# clock.net
KiCad netlist of a schematic drawn in EAGLE
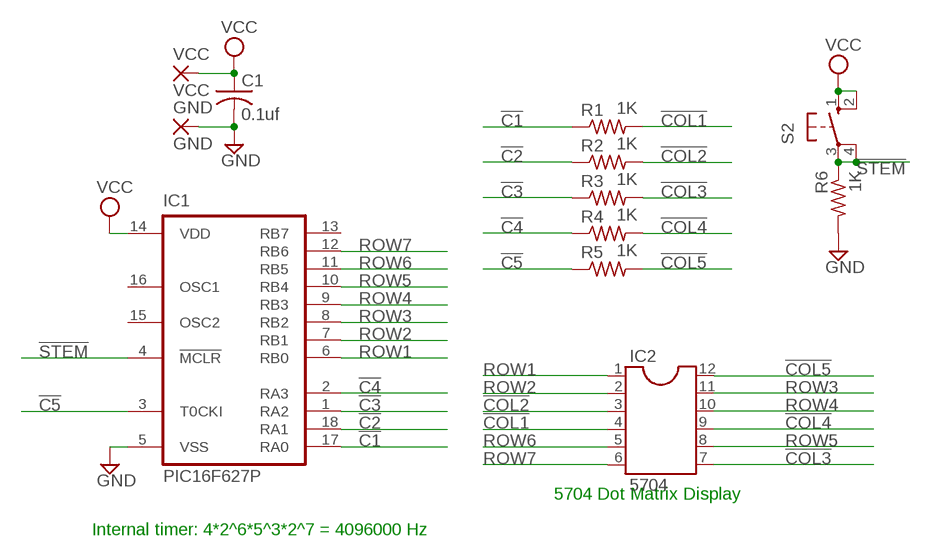
[diagram p0: schematic, sheet 1]

(export (version "E")
  (design (tool "Eeschema 10.0.6"))
  (components
    (comp (ref "C1")
      (value "0.1uf")
      (footprint "eagle-import:C025-025X050")
      (libsource (lib "eagle-import") (part "C-US025-025X050"))
    )
    (comp (ref "GND")
      (value "GND")
      (footprint "eagle-import:1,6_0,8")
      (libsource (lib "eagle-import") (part "1,6/0,8"))
    )
    (comp (ref "IC1")
      (value "PIC16F627P")
      (footprint "eagle-import:DIL18")
      (fields (field (name "MF") "MICROCHIP") (field (name "MPN") "PIC16C622A-04I/P"))
      (libsource (lib "eagle-import") (part "PIC16CP622"))
    )
    (comp (ref "IC2")
      (value "5704")
      (footprint "eagle-import:DIL12")
      (libsource (lib "eagle-import") (part "DIL12"))
    )
    (comp (ref "R1")
      (value "1K")
      (footprint "eagle-import:0207_10")
      (libsource (lib "eagle-import") (part "R-US_0207/10"))
    )
    (comp (ref "R2")
      (value "1K")
      (footprint "eagle-import:0207_10")
      (libsource (lib "eagle-import") (part "R-US_0207/10"))
    )
    (comp (ref "R3")
      (value "1K")
      (footprint "eagle-import:0207_10")
      (libsource (lib "eagle-import") (part "R-US_0207/10"))
    )
    (comp (ref "R4")
      (value "1K")
      (footprint "eagle-import:0207_10")
      (libsource (lib "eagle-import") (part "R-US_0207/10"))
    )
    (comp (ref "R5")
      (value "1K")
      (footprint "eagle-import:0207_10")
      (libsource (lib "eagle-import") (part "R-US_0207/10"))
    )
    (comp (ref "R6")
      (value "1K")
      (footprint "eagle-import:0207_10")
      (libsource (lib "eagle-import") (part "R-US_0207/10"))
    )
    (comp (ref "S2")
      (value "10-XX")
      (footprint "eagle-import:B3F-10XX")
      (fields (field (name "MPN") "B3F-1000"))
      (libsource (lib "eagle-import") (part "10-XX"))
    )
    (comp (ref "VCC")
      (value "VCC")
      (footprint "eagle-import:1,6_0,8")
      (libsource (lib "eagle-import") (part "1,6/0,8"))
    )
  )
  (nets
    (net (code "1") (name "/ROW1") (class "Default")
      (node (ref "IC1") (pin "6") (pinfunction "RB0_6") (pintype "bidirectional"))
      (node (ref "IC2") (pin "1") (pinfunction "1_1") (pintype "passive"))
    )
    (net (code "2") (name "/ROW2") (class "Default")
      (node (ref "IC1") (pin "7") (pinfunction "RB1_7") (pintype "bidirectional"))
      (node (ref "IC2") (pin "2") (pinfunction "2_2") (pintype "passive"))
    )
    (net (code "3") (name "/ROW3") (class "Default")
      (node (ref "IC1") (pin "8") (pinfunction "RB2_8") (pintype "bidirectional"))
      (node (ref "IC2") (pin "11") (pinfunction "11_11") (pintype "passive"))
    )
    (net (code "4") (name "/ROW4") (class "Default")
      (node (ref "IC1") (pin "9") (pinfunction "RB3_9") (pintype "bidirectional"))
      (node (ref "IC2") (pin "10") (pinfunction "10_10") (pintype "passive"))
    )
    (net (code "5") (name "/ROW5") (class "Default")
      (node (ref "IC1") (pin "10") (pinfunction "RB4_10") (pintype "bidirectional"))
      (node (ref "IC2") (pin "8") (pinfunction "8_8") (pintype "passive"))
    )
    (net (code "6") (name "/ROW6") (class "Default")
      (node (ref "IC1") (pin "11") (pinfunction "RB5_11") (pintype "bidirectional"))
      (node (ref "IC2") (pin "5") (pinfunction "5_5") (pintype "passive"))
    )
    (net (code "7") (name "/ROW7") (class "Default")
      (node (ref "IC1") (pin "12") (pinfunction "RB6_12") (pintype "bidirectional"))
      (node (ref "IC2") (pin "6") (pinfunction "6_6") (pintype "passive"))
    )
    (net (code "8") (name "/~{C1}") (class "Default")
      (node (ref "IC1") (pin "17") (pinfunction "RA0_17") (pintype "bidirectional"))
      (node (ref "R1") (pin "1") (pinfunction "1_1") (pintype "passive"))
    )
    (net (code "9") (name "/~{C2}") (class "Default")
      (node (ref "IC1") (pin "18") (pinfunction "RA1_18") (pintype "bidirectional"))
      (node (ref "R2") (pin "1") (pinfunction "1_1") (pintype "passive"))
    )
    (net (code "10") (name "/~{C3}") (class "Default")
      (node (ref "IC1") (pin "1") (pinfunction "RA2_1") (pintype "bidirectional"))
      (node (ref "R3") (pin "1") (pinfunction "1_1") (pintype "passive"))
    )
    (net (code "11") (name "/~{C4}") (class "Default")
      (node (ref "IC1") (pin "2") (pinfunction "RA3_2") (pintype "bidirectional"))
      (node (ref "R4") (pin "1") (pinfunction "1_1") (pintype "passive"))
    )
    (net (code "12") (name "/~{C5}") (class "Default")
      (node (ref "IC1") (pin "3") (pinfunction "T0CKI_3") (pintype "input"))
      (node (ref "R5") (pin "1") (pinfunction "1_1") (pintype "passive"))
    )
    (net (code "13") (name "/~{COL1}") (class "Default")
      (node (ref "IC2") (pin "4") (pinfunction "4_4") (pintype "passive"))
      (node (ref "R1") (pin "2") (pinfunction "2_2") (pintype "passive"))
    )
    (net (code "14") (name "/~{COL2}") (class "Default")
      (node (ref "IC2") (pin "3") (pinfunction "3_3") (pintype "passive"))
      (node (ref "R2") (pin "2") (pinfunction "2_2") (pintype "passive"))
    )
    (net (code "15") (name "/~{COL3}") (class "Default")
      (node (ref "IC2") (pin "7") (pinfunction "7_7") (pintype "passive"))
      (node (ref "R3") (pin "2") (pinfunction "2_2") (pintype "passive"))
    )
    (net (code "16") (name "/~{COL4}") (class "Default")
      (node (ref "IC2") (pin "9") (pinfunction "9_9") (pintype "passive"))
      (node (ref "R4") (pin "2") (pinfunction "2_2") (pintype "passive"))
    )
    (net (code "17") (name "/~{COL5}") (class "Default")
      (node (ref "IC2") (pin "12") (pinfunction "12_12") (pintype "passive"))
      (node (ref "R5") (pin "2") (pinfunction "2_2") (pintype "passive"))
    )
    (net (code "18") (name "/~{STEM}") (class "Default")
      (node (ref "IC1") (pin "4") (pinfunction "~{MCLR}_4") (pintype "input"))
      (node (ref "R6") (pin "1") (pinfunction "1_1") (pintype "passive"))
      (node (ref "S2") (pin "3") (pinfunction "P_3") (pintype "passive"))
      (node (ref "S2") (pin "4") (pinfunction "P1_4") (pintype "passive"))
    )
    (net (code "19") (name "GND") (class "Default")
      (node (ref "C1") (pin "2") (pinfunction "2_2") (pintype "passive"))
      (node (ref "GND") (pin "1") (pinfunction "P_1") (pintype "passive"))
      (node (ref "IC1") (pin "5") (pinfunction "VSS_5") (pintype "power_in"))
      (node (ref "R6") (pin "2") (pinfunction "2_2") (pintype "passive"))
    )
    (net (code "20") (name "VCC") (class "Default")
      (node (ref "C1") (pin "1") (pinfunction "1_1") (pintype "passive"))
      (node (ref "IC1") (pin "14") (pinfunction "VDD_14") (pintype "power_in"))
      (node (ref "S2") (pin "1") (pinfunction "S_1") (pintype "passive"))
      (node (ref "S2") (pin "2") (pinfunction "S1_2") (pintype "passive"))
      (node (ref "VCC") (pin "1") (pinfunction "P_1") (pintype "passive"))
    )
    (net (code "21") (name "unconnected-(IC1-OSC1-Pad16)") (class "Default")
      (node (ref "IC1") (pin "16") (pinfunction "OSC1_16") (pintype "input"))
    )
    (net (code "22") (name "unconnected-(IC1-OSC2-Pad15)") (class "Default")
      (node (ref "IC1") (pin "15") (pinfunction "OSC2_15") (pintype "output"))
    )
    (net (code "23") (name "unconnected-(IC1-RB7-Pad13)") (class "Default")
      (node (ref "IC1") (pin "13") (pinfunction "RB7_13") (pintype "bidirectional"))
    )
  )
)
